# si4732__3_1__2869_427_420.net
KiCad netlist of a schematic drawn in EasyEDA Pro
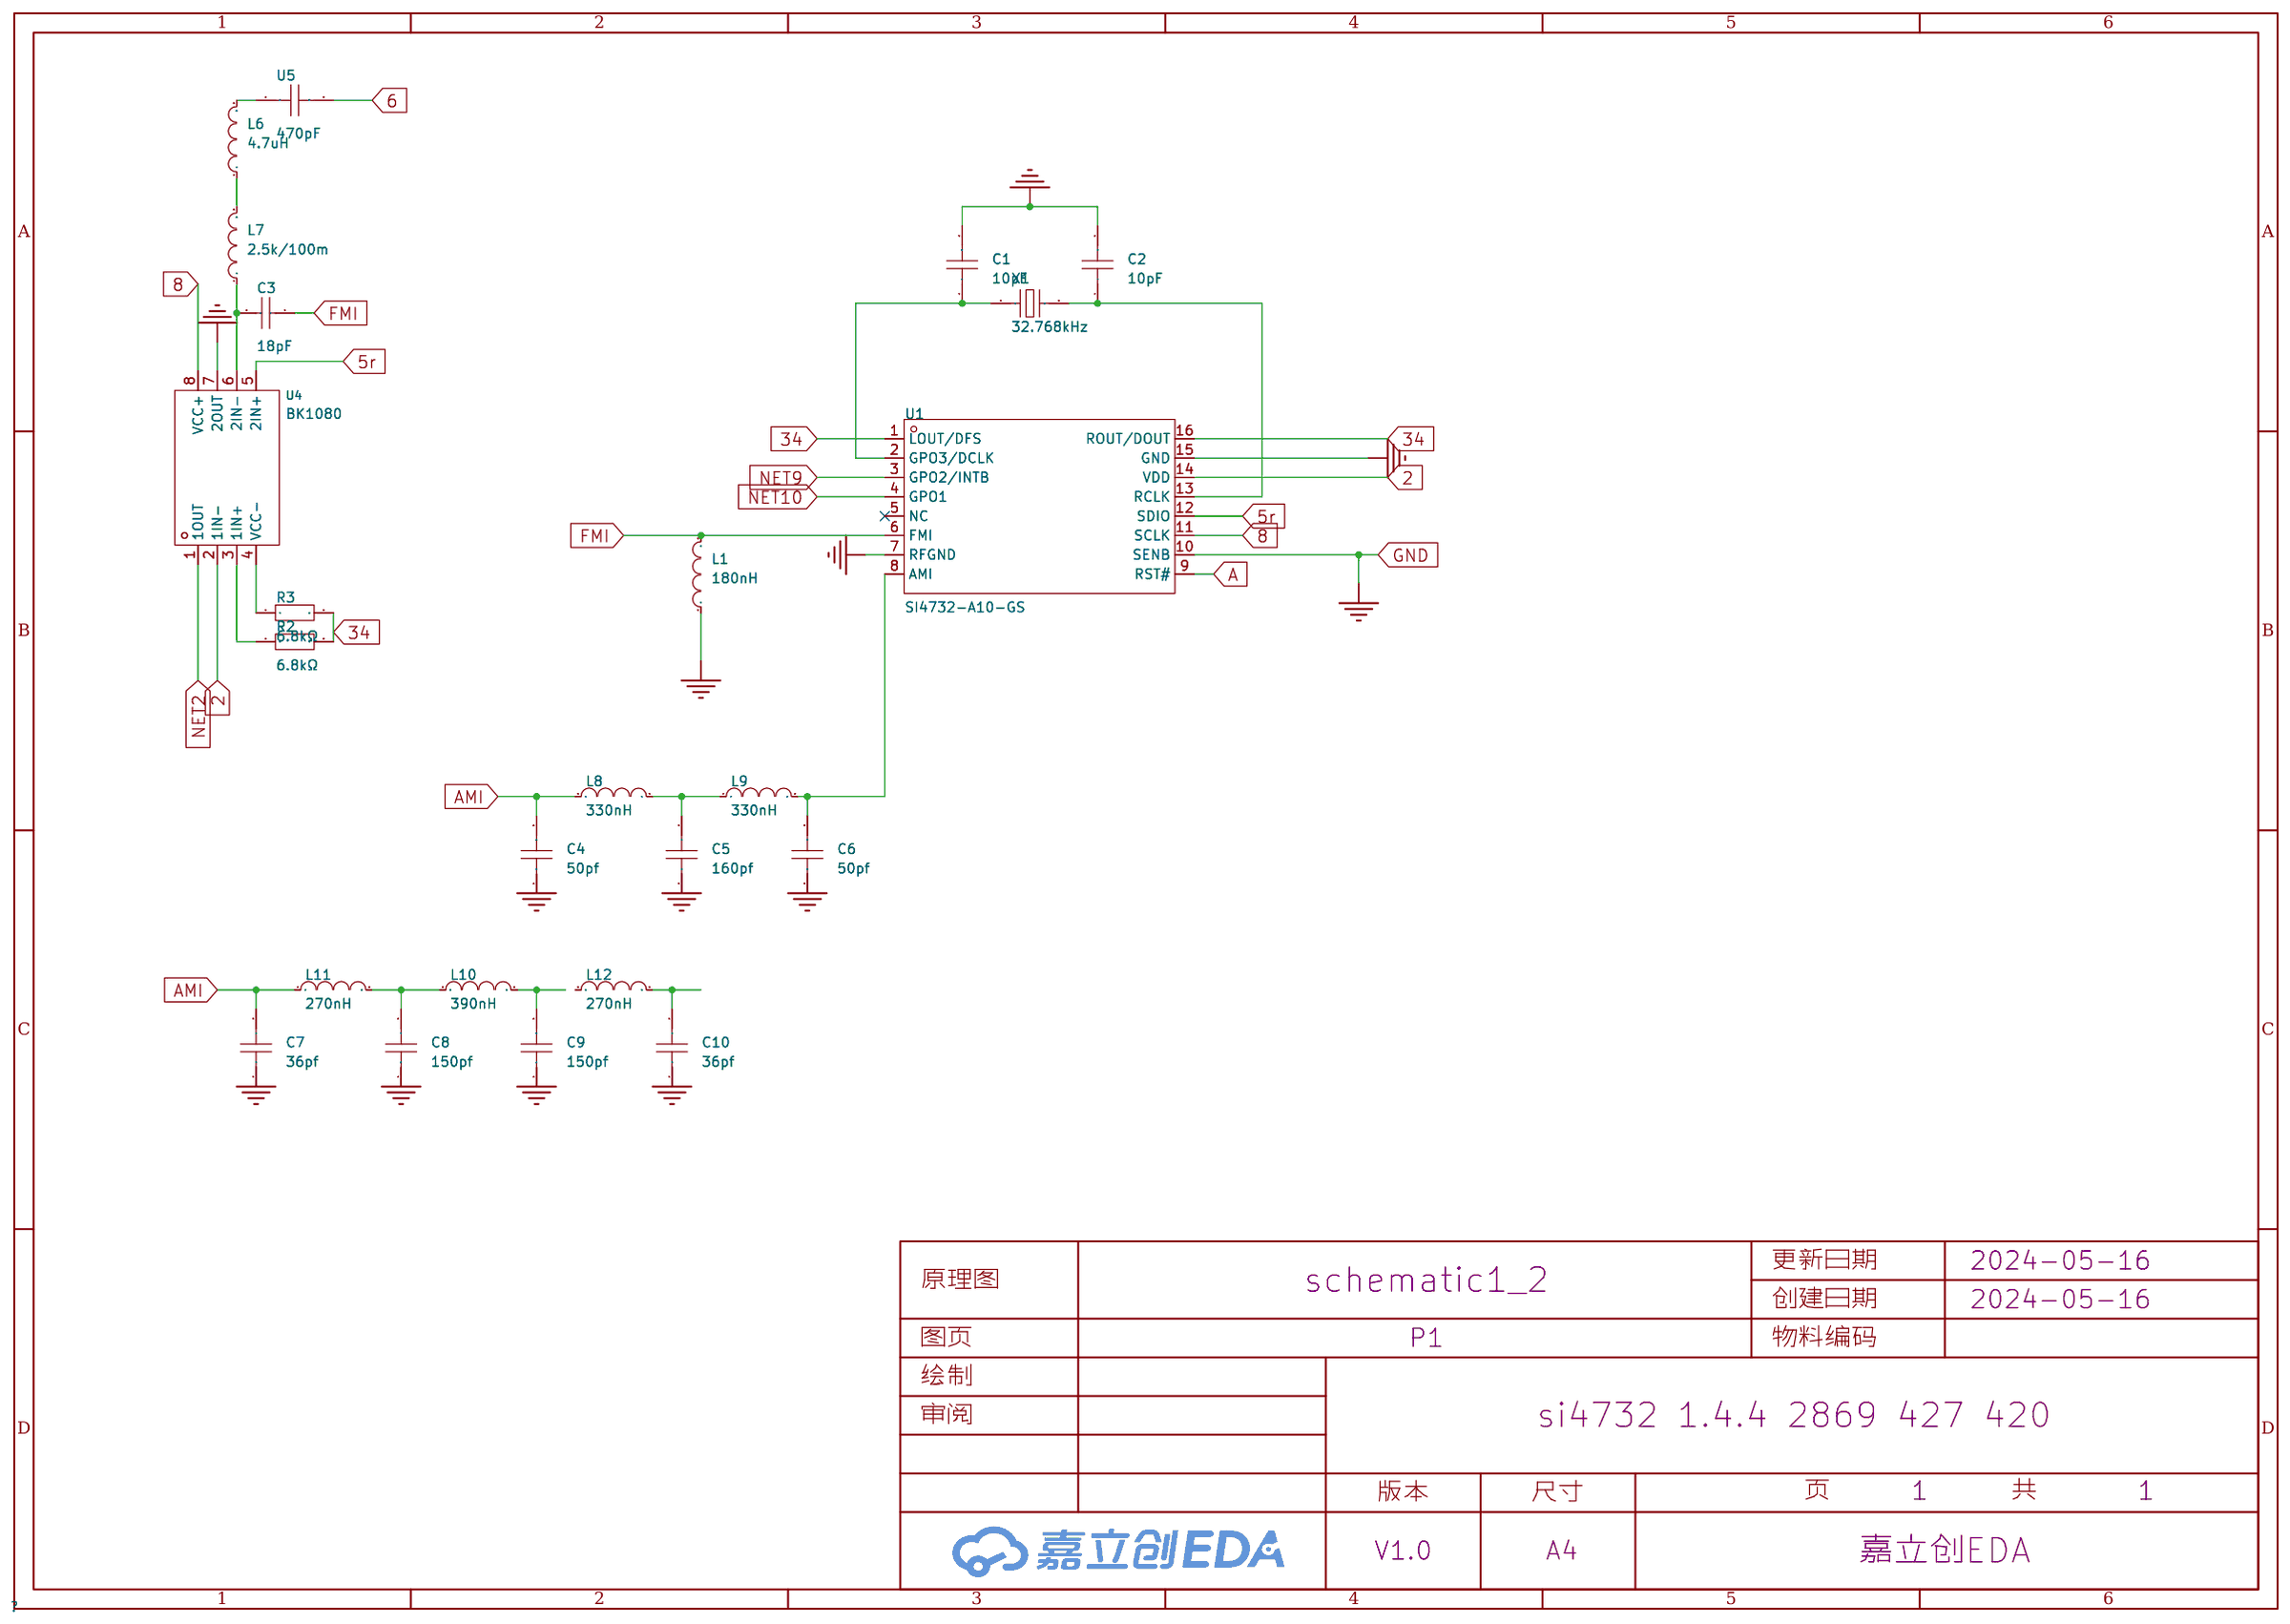
[diagram p0: schematic sheet]

(export (version "E")
  (design (tool "Eeschema 10.0.6"))
  (components
    (comp (ref "C1")
      (value "10pF")
      (footprint "easyedapro:C0402")
      (description "容值:10pF;精度:±5%;额定电压:50V;材质(温度系数):C0G;")
      (fields
        (field (name "Manufacturer Part") "CL05C100JB5NNNC")
        (field (name "Manufacturer") "SAMSUNG(三星)")
      )
      (libsource (lib "easyedapro") (part "CL05C100JB5NNNC"))
    )
    (comp (ref "C2")
      (value "10pF")
      (footprint "easyedapro:C0402")
      (description "容值:10pF;精度:±5%;额定电压:50V;材质(温度系数):C0G;")
      (fields
        (field (name "Manufacturer Part") "CL05C100JB5NNNC")
        (field (name "Manufacturer") "SAMSUNG(三星)")
      )
      (libsource (lib "easyedapro") (part "CL05C100JB5NNNC"))
    )
    (comp (ref "C3")
      (value "18pF")
      (footprint "easyedapro:C0402")
      (description "容值:18pF;精度:±5%;额定电压:50V;材质(温度系数):C0G;")
      (fields (field (name "Manufacturer Part") "0402CG180J500NT") (field (name "Manufacturer") "FH(风华)"))
      (libsource (lib "easyedapro") (part "0402CG180J500NT"))
    )
    (comp (ref "C4")
      (value "50pf")
      (footprint "easyedapro:C0603")
      (libsource (lib "easyedapro") (part "CapAcitance"))
    )
    (comp (ref "C5")
      (value "160pf")
      (footprint "easyedapro:C0603")
      (libsource (lib "easyedapro") (part "CapAcitance"))
    )
    (comp (ref "C6")
      (value "50pf")
      (footprint "easyedapro:C0603")
      (libsource (lib "easyedapro") (part "CapAcitance"))
    )
    (comp (ref "C7")
      (value "36pf")
      (footprint "easyedapro:C0603")
      (libsource (lib "easyedapro") (part "CapAcitance"))
    )
    (comp (ref "C8")
      (value "150pf")
      (footprint "easyedapro:C0603")
      (libsource (lib "easyedapro") (part "CapAcitance"))
    )
    (comp (ref "C9")
      (value "150pf")
      (footprint "easyedapro:C0603")
      (libsource (lib "easyedapro") (part "CapAcitance"))
    )
    (comp (ref "C10")
      (value "36pf")
      (footprint "easyedapro:C0603")
      (libsource (lib "easyedapro") (part "CapAcitance"))
    )
    (comp (ref "L1")
      (value "180nH")
      (footprint "easyedapro:L0402")
      (description "电感值:180nH;精度:±5%;额定电流:240mA;饱和电流(Isat):-;直流电阻(DCR):2.5Ω;")
      (fields
        (field (name "Manufacturer Part") "SDWL1005CHR18JSTF")
        (field (name "Manufacturer") "Sunlord(顺络)")
      )
      (libsource (lib "easyedapro") (part "SDWL1005CHR18JSTF"))
    )
    (comp (ref "L6")
      (value "4.7uH")
      (fields (field (name "Manufacturer Part") "CMP201209UD4R7KT") (field (name "Manufacturer") "FH(风华)"))
      (libsource (lib "easyedapro") (part "DFE252010F-4R7M=P2"))
    )
    (comp (ref "L7")
      (value "2.5k/100m")
      (footprint "easyedapro:L0603")
      (libsource (lib "easyedapro") (part "SDFL1608S100KTF"))
    )
    (comp (ref "L8")
      (value "330nH")
      (footprint "easyedapro:L0603")
      (libsource (lib "easyedapro") (part "SDFL1608S100KTF"))
    )
    (comp (ref "L9")
      (value "330nH")
      (footprint "easyedapro:L0603")
      (libsource (lib "easyedapro") (part "SDFL1608S100KTF"))
    )
    (comp (ref "L10")
      (value "390nH")
      (footprint "easyedapro:L0603")
      (libsource (lib "easyedapro") (part "SDFL1608S100KTF"))
    )
    (comp (ref "L11")
      (value "270nH")
      (footprint "easyedapro:L0603")
      (libsource (lib "easyedapro") (part "SDFL1608S100KTF"))
    )
    (comp (ref "L12")
      (value "270nH")
      (footprint "easyedapro:L0603")
      (libsource (lib "easyedapro") (part "SDFL1608S100KTF"))
    )
    (comp (ref "R2")
      (value "6.8kΩ")
      (footprint "easyedapro:R0402")
      (description "电阻类型:厚膜电阻;阻值:6.8kΩ;精度:±5%;功率:100mW;最大工作电压:50V;温度系数:±200ppm/°C;")
      (fields (field (name "Manufacturer Part") "RK73B1ETTP682J") (field (name "Manufacturer") "KOA"))
      (libsource (lib "easyedapro") (part "RK73B1ETTP682J"))
    )
    (comp (ref "R3")
      (value "6.8kΩ")
      (footprint "easyedapro:R0402")
      (description "电阻类型:厚膜电阻;阻值:6.8kΩ;精度:±5%;功率:100mW;最大工作电压:50V;温度系数:±200ppm/°C;")
      (fields (field (name "Manufacturer Part") "RK73B1ETTP682J") (field (name "Manufacturer") "KOA"))
      (libsource (lib "easyedapro") (part "RK73B1ETTP682J"))
    )
    (comp (ref "U1")
      (value "SI4732-A10-GS")
      (footprint "easyedapro:SOIC-16_L9.9-W3.9-P1.27-LS6.0-BL")
      (fields (field (name "Manufacturer") "SKYWORKS/SILICON LABS(芯科)"))
      (libsource (lib "easyedapro") (part "SI4732-A10-GS"))
    )
    (comp (ref "U4")
      (value "BK1080")
      (footprint "easyedapro:SOIC-8_L5.0-W4.0-P1.27-LS6.0-BL")
      (description "放大器数:双路;增益带宽积(GBP):4MHz;输入偏置电流(Ib):20pA;输入失调电压(Vos):3mV;压摆率(SR):16V/us;轨到轨:-;")
      (fields (field (name "Manufacturer") "ST(意法半导体)"))
      (libsource (lib "easyedapro") (part "TL072CDT"))
    )
    (comp (ref "U5")
      (value "470pF")
      (footprint "easyedapro:C0402")
      (description "容值:470pF;精度:±10%;额定电压:100V;材质(温度系数):CH;")
      (fields (field (name "Manufacturer Part") "C1005CH2A471K050BA") (field (name "Manufacturer") "TDK"))
      (libsource (lib "easyedapro") (part "C1005CH2A471K050BA"))
    )
    (comp (ref "X1")
      (value "32.768kHz")
      (footprint "easyedapro:OSC-SMD_L3.2-W1.5")
      (description "晶振类型:贴片晶振;频率:32.768kHz;常温频差:±20ppm;外接负载电容:12.5pF;")
      (fields (field (name "Manufacturer Part") "X321532768KGD2SI") (field (name "Manufacturer") "YXC(扬兴晶振)"))
      (libsource (lib "easyedapro") (part "X321532768KGD2SI"))
    )
  )
  (nets
    (net (code "1") (name "2") (class "Default")
      (node (ref "U1") (pin "14") (pinfunction "VDD_14") (pintype "unspecified"))
      (node (ref "U4") (pin "2") (pinfunction "1IN-_2") (pintype "input"))
    )
    (net (code "2") (name "5r") (class "Default")
      (node (ref "U1") (pin "12") (pinfunction "SDIO_12") (pintype "unspecified"))
      (node (ref "U4") (pin "5") (pinfunction "2IN+_5") (pintype "input"))
    )
    (net (code "3") (name "6") (class "Default")
      (node (ref "U5") (pin "2") (pinfunction "2_2") (pintype "input"))
    )
    (net (code "4") (name "8") (class "Default")
      (node (ref "U1") (pin "11") (pinfunction "SCLK_11") (pintype "unspecified"))
      (node (ref "U4") (pin "8") (pinfunction "VCC+_8") (pintype "input"))
    )
    (net (code "5") (name "34") (class "Default")
      (node (ref "R2") (pin "2") (pinfunction "2_2") (pintype "input"))
      (node (ref "R3") (pin "2") (pinfunction "2_2") (pintype "input"))
      (node (ref "U1") (pin "1") (pinfunction "LOUT/DFS_1") (pintype "unspecified"))
      (node (ref "U1") (pin "16") (pinfunction "ROUT/DOUT_16") (pintype "unspecified"))
    )
    (net (code "6") (name "A") (class "Default")
      (node (ref "U1") (pin "9") (pinfunction "RST#_9") (pintype "unspecified"))
    )
    (net (code "7") (name "AMI") (class "Default")
      (node (ref "C4") (pin "2") (pinfunction "2_2") (pintype "input"))
      (node (ref "C7") (pin "2") (pinfunction "2_2") (pintype "input"))
      (node (ref "L11") (pin "1") (pinfunction "1_1") (pintype "unspecified"))
      (node (ref "L8") (pin "1") (pinfunction "1_1") (pintype "unspecified"))
    )
    (net (code "8") (name "FMI") (class "Default")
      (node (ref "C3") (pin "1") (pinfunction "1_1") (pintype "input"))
      (node (ref "L1") (pin "2") (pinfunction "2_2") (pintype "unspecified"))
      (node (ref "U1") (pin "6") (pinfunction "FMI_6") (pintype "unspecified"))
    )
    (net (code "9") (name "GND") (class "Default")
      (node (ref "C1") (pin "2") (pinfunction "2_2") (pintype "unspecified"))
      (node (ref "C10") (pin "1") (pinfunction "1_1") (pintype "input"))
      (node (ref "C2") (pin "2") (pinfunction "2_2") (pintype "unspecified"))
      (node (ref "C4") (pin "1") (pinfunction "1_1") (pintype "input"))
      (node (ref "C5") (pin "1") (pinfunction "1_1") (pintype "input"))
      (node (ref "C6") (pin "1") (pinfunction "1_1") (pintype "input"))
      (node (ref "C7") (pin "1") (pinfunction "1_1") (pintype "input"))
      (node (ref "C8") (pin "1") (pinfunction "1_1") (pintype "input"))
      (node (ref "C9") (pin "1") (pinfunction "1_1") (pintype "input"))
      (node (ref "L1") (pin "1") (pinfunction "1_1") (pintype "unspecified"))
      (node (ref "U1") (pin "10") (pinfunction "SENB_10") (pintype "unspecified"))
      (node (ref "U1") (pin "15") (pinfunction "GND_15") (pintype "unspecified"))
      (node (ref "U1") (pin "7") (pinfunction "RFGND_7") (pintype "unspecified"))
      (node (ref "U4") (pin "7") (pinfunction "2OUT_7") (pintype "input"))
    )
    (net (code "10") (name "NET2") (class "Default")
      (node (ref "U4") (pin "1") (pinfunction "1OUT_1") (pintype "input"))
    )
    (net (code "11") (name "NET9") (class "Default")
      (node (ref "U1") (pin "3") (pinfunction "GPO2/INTB_3") (pintype "unspecified"))
    )
    (net (code "12") (name "NET10") (class "Default")
      (node (ref "U1") (pin "4") (pinfunction "GPO1_4") (pintype "unspecified"))
    )
    (net (code "13") (name "Net-(C5-Pad2)") (class "Default")
      (node (ref "C5") (pin "2") (pinfunction "2_2") (pintype "input"))
      (node (ref "L8") (pin "2") (pinfunction "2_2") (pintype "unspecified"))
      (node (ref "L9") (pin "1") (pinfunction "1_1") (pintype "unspecified"))
    )
    (net (code "14") (name "Net-(C8-Pad2)") (class "Default")
      (node (ref "C8") (pin "2") (pinfunction "2_2") (pintype "input"))
      (node (ref "L10") (pin "1") (pinfunction "1_1") (pintype "unspecified"))
      (node (ref "L11") (pin "2") (pinfunction "2_2") (pintype "unspecified"))
    )
    (net (code "15") (name "Net-(C9-Pad2)") (class "Default")
      (node (ref "C9") (pin "2") (pinfunction "2_2") (pintype "input"))
      (node (ref "L10") (pin "2") (pinfunction "2_2") (pintype "unspecified"))
    )
    (net (code "16") (name "Net-(C10-Pad2)") (class "Default")
      (node (ref "C10") (pin "2") (pinfunction "2_2") (pintype "input"))
      (node (ref "L12") (pin "2") (pinfunction "2_2") (pintype "unspecified"))
    )
    (net (code "17") (name "Net-(L6-Pad1)") (class "Default")
      (node (ref "L6") (pin "1") (pinfunction "1_1") (pintype "unspecified"))
      (node (ref "L7") (pin "2") (pinfunction "2_2") (pintype "unspecified"))
    )
    (net (code "18") (name "Net-(L6-Pad2)") (class "Default")
      (node (ref "L6") (pin "2") (pinfunction "2_2") (pintype "unspecified"))
      (node (ref "U5") (pin "1") (pinfunction "1_1") (pintype "input"))
    )
    (net (code "19") (name "Net-(U1-AMI)") (class "Default")
      (node (ref "C6") (pin "2") (pinfunction "2_2") (pintype "input"))
      (node (ref "L9") (pin "2") (pinfunction "2_2") (pintype "unspecified"))
      (node (ref "U1") (pin "8") (pinfunction "AMI_8") (pintype "unspecified"))
    )
    (net (code "20") (name "Net-(U1-GPO3{slash}DCLK)") (class "Default")
      (node (ref "C1") (pin "1") (pinfunction "1_1") (pintype "unspecified"))
      (node (ref "U1") (pin "2") (pinfunction "GPO3/DCLK_2") (pintype "unspecified"))
      (node (ref "X1") (pin "1") (pinfunction "1_1") (pintype "input"))
    )
    (net (code "21") (name "Net-(U1-RCLK)") (class "Default")
      (node (ref "C2") (pin "1") (pinfunction "1_1") (pintype "unspecified"))
      (node (ref "U1") (pin "13") (pinfunction "RCLK_13") (pintype "unspecified"))
      (node (ref "X1") (pin "2") (pinfunction "2_2") (pintype "input"))
    )
    (net (code "22") (name "Net-(U4-1IN+)") (class "Default")
      (node (ref "R2") (pin "1") (pinfunction "1_1") (pintype "input"))
      (node (ref "U4") (pin "3") (pinfunction "1IN+_3") (pintype "input"))
    )
    (net (code "23") (name "Net-(U4-2IN-)") (class "Default")
      (node (ref "C3") (pin "2") (pinfunction "2_2") (pintype "input"))
      (node (ref "L7") (pin "1") (pinfunction "1_1") (pintype "unspecified"))
      (node (ref "U4") (pin "6") (pinfunction "2IN-_6") (pintype "input"))
    )
    (net (code "24") (name "Net-(U4-VCC-)") (class "Default")
      (node (ref "R3") (pin "1") (pinfunction "1_1") (pintype "input"))
      (node (ref "U4") (pin "4") (pinfunction "VCC-_4") (pintype "input"))
    )
    (net (code "25") (name "unconnected-(L12-Pad1)") (class "Default")
      (node (ref "L12") (pin "1") (pinfunction "1_1") (pintype "unspecified"))
    )
    (net (code "26") (name "unconnected-(U1-NC-Pad5)") (class "Default")
      (node (ref "U1") (pin "5") (pinfunction "NC_5") (pintype "unspecified+no_connect"))
    )
  )
)
